# Sch-Bicycle-LED_Lamp_Brd.net
KiCad netlist of a schematic drawn in Altium Designer
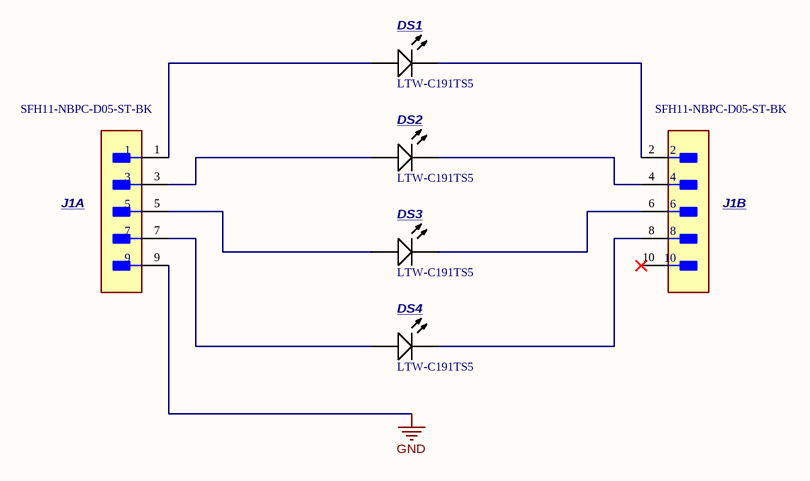
[diagram p0:  Sch-Bicycle-LED_Lamp Brd.SchDoc]

(export (version "E")
  (design (tool "Eeschema 10.0.6"))
  (components
    (comp (ref "DS1")
      (value "LTW-C191TS5")
      (footprint "LTST-LTW-C191TS5_V")
      (description "LED Uni-Color White, 70 mW, 20 mA, -20 to 80 degC, 2-Pin SMD, RoHS, Tape and Reel")
      (fields (field (name "POWER") "70mW") (field (name "MANUFACTURER") "Lite-On"))
      (libsource (lib "Altium Designer Advanced Training Course 2 - A365") (part "LED-WHITE-AK-2"))
    )
    (comp (ref "DS2")
      (value "LTW-C191TS5")
      (footprint "LTST-LTW-C191TS5_V")
      (description "LED Uni-Color White, 70 mW, 20 mA, -20 to 80 degC, 2-Pin SMD, RoHS, Tape and Reel")
      (fields (field (name "POWER") "70mW") (field (name "MANUFACTURER") "Lite-On"))
      (libsource (lib "Altium Designer Advanced Training Course 2 - A365") (part "LED-WHITE-AK-2"))
    )
    (comp (ref "DS3")
      (value "LTW-C191TS5")
      (footprint "LTST-LTW-C191TS5_V")
      (description "LED Uni-Color White, 70 mW, 20 mA, -20 to 80 degC, 2-Pin SMD, RoHS, Tape and Reel")
      (fields (field (name "POWER") "70mW") (field (name "MANUFACTURER") "Lite-On"))
      (libsource (lib "Altium Designer Advanced Training Course 2 - A365") (part "LED-WHITE-AK-2"))
    )
    (comp (ref "DS4")
      (value "LTW-C191TS5")
      (footprint "LTST-LTW-C191TS5_V")
      (description "LED Uni-Color White, 70 mW, 20 mA, -20 to 80 degC, 2-Pin SMD, RoHS, Tape and Reel")
      (fields (field (name "POWER") "70mW") (field (name "MANUFACTURER") "Lite-On"))
      (libsource (lib "Altium Designer Advanced Training Course 2 - A365") (part "LED-WHITE-AK-2"))
    )
    (comp (ref "J1")
      (value "SFH11-NBPC-D05-ST-BK")
      (footprint "SFH11-NBPC-D05-ST-BK-Footprint-1")
      (description "Conn Hdr 10POS 0.1 Gold Pcb")
      (libsource (lib "Altium Designer Advanced Training Course 2 - A365") (part "b90c43bfdb997d6037ddb7f87098795"))
    )
  )
  (nets
    (net (code "1") (name "GND") (class "Default")
      (node (ref "J1") (pin "9") (pinfunction "9_9") (pintype "passive"))
    )
    (net (code "2") (name "Net-(DS1-A)") (class "Default")
      (node (ref "DS1") (pin "1") (pinfunction "A_1") (pintype "passive"))
      (node (ref "J1") (pin "1") (pinfunction "1_1") (pintype "passive"))
    )
    (net (code "3") (name "Net-(DS1-K)") (class "Default")
      (node (ref "DS1") (pin "2") (pinfunction "K_2") (pintype "passive"))
      (node (ref "J1") (pin "2") (pinfunction "2_2") (pintype "passive"))
    )
    (net (code "4") (name "Net-(DS2-A)") (class "Default")
      (node (ref "DS2") (pin "1") (pinfunction "A_1") (pintype "passive"))
      (node (ref "J1") (pin "3") (pinfunction "3_3") (pintype "passive"))
    )
    (net (code "5") (name "Net-(DS2-K)") (class "Default")
      (node (ref "DS2") (pin "2") (pinfunction "K_2") (pintype "passive"))
      (node (ref "J1") (pin "4") (pinfunction "4_4") (pintype "passive"))
    )
    (net (code "6") (name "Net-(DS3-A)") (class "Default")
      (node (ref "DS3") (pin "1") (pinfunction "A_1") (pintype "passive"))
      (node (ref "J1") (pin "5") (pinfunction "5_5") (pintype "passive"))
    )
    (net (code "7") (name "Net-(DS3-K)") (class "Default")
      (node (ref "DS3") (pin "2") (pinfunction "K_2") (pintype "passive"))
      (node (ref "J1") (pin "6") (pinfunction "6_6") (pintype "passive"))
    )
    (net (code "8") (name "Net-(DS4-A)") (class "Default")
      (node (ref "DS4") (pin "1") (pinfunction "A_1") (pintype "passive"))
      (node (ref "J1") (pin "7") (pinfunction "7_7") (pintype "passive"))
    )
    (net (code "9") (name "Net-(DS4-K)") (class "Default")
      (node (ref "DS4") (pin "2") (pinfunction "K_2") (pintype "passive"))
      (node (ref "J1") (pin "8") (pinfunction "8_8") (pintype "passive"))
    )
    (net (code "10") (name "unconnected-(J1-Pad10)") (class "Default")
      (node (ref "J1") (pin "10") (pinfunction "10_10") (pintype "passive+no_connect"))
    )
  )
)
